# Control_module.net
KiCad netlist of a schematic drawn in Altium Designer
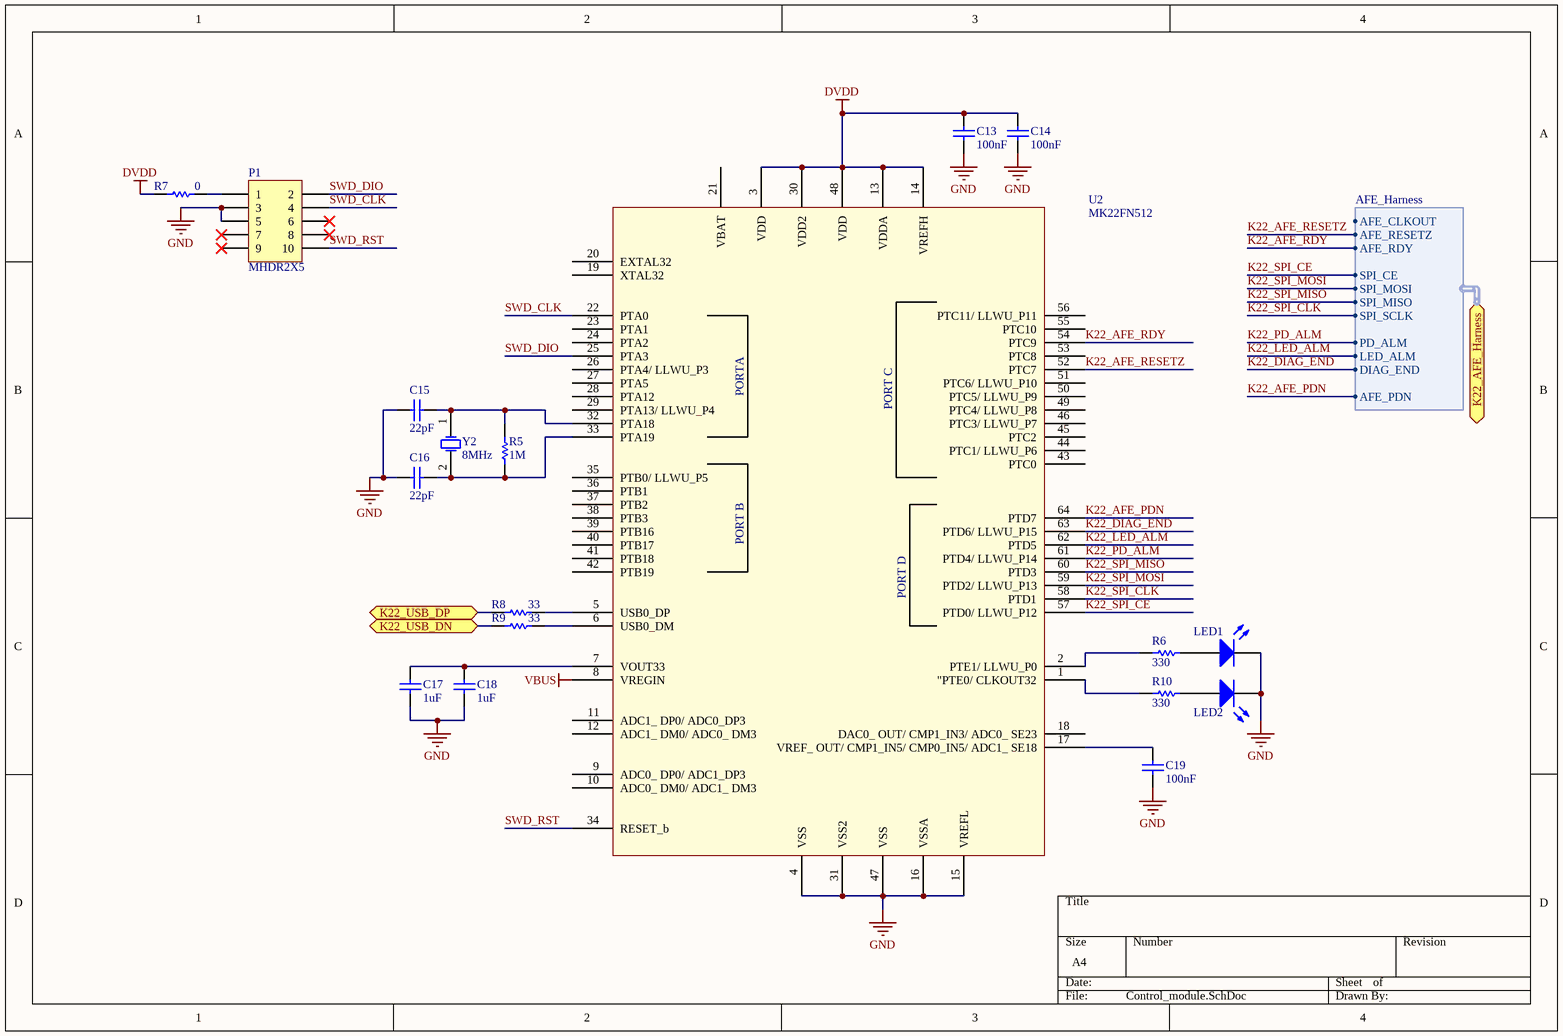
[diagram p0: Control_module.SchDoc]

(export (version "E")
  (design (tool "Eeschema 10.0.6"))
  (components
    (comp (ref "C13")
      (value "100nF")
      (footprint "6-0805_M")
      (description "Capacitor")
      (fields (field (name "Comment") "Cap") (field (name "PUBLISHER") "Altium Limited"))
      (libsource (lib "Miscellaneous Devices") (part "Cap"))
    )
    (comp (ref "C14")
      (value "100nF")
      (footprint "6-0805_M")
      (description "Capacitor")
      (fields (field (name "Comment") "Cap") (field (name "PUBLISHER") "Altium Limited"))
      (libsource (lib "Miscellaneous Devices") (part "Cap"))
    )
    (comp (ref "C15")
      (value "22pF")
      (footprint "6-0805_M")
      (description "Capacitor")
      (fields (field (name "Comment") "Cap") (field (name "PUBLISHER") "Altium Limited"))
      (libsource (lib "Miscellaneous Devices") (part "Cap"))
    )
    (comp (ref "C16")
      (value "22pF")
      (footprint "6-0805_M")
      (description "Capacitor")
      (fields (field (name "Comment") "Cap") (field (name "PUBLISHER") "Altium Limited"))
      (libsource (lib "Miscellaneous Devices") (part "Cap"))
    )
    (comp (ref "C17")
      (value "1uF")
      (footprint "6-0805_M")
      (description "Capacitor")
      (fields (field (name "Comment") "Cap") (field (name "PUBLISHER") "Altium Limited"))
      (libsource (lib "Miscellaneous Devices") (part "Cap"))
    )
    (comp (ref "C18")
      (value "1uF")
      (footprint "6-0805_M")
      (description "Capacitor")
      (fields (field (name "Comment") "Cap") (field (name "PUBLISHER") "Altium Limited"))
      (libsource (lib "Miscellaneous Devices") (part "Cap"))
    )
    (comp (ref "C19")
      (value "100nF")
      (footprint "6-0805_M")
      (description "Capacitor")
      (fields (field (name "Comment") "Cap") (field (name "PUBLISHER") "Altium Limited"))
      (libsource (lib "Miscellaneous Devices") (part "Cap"))
    )
    (comp (ref "LED1")
      (value "LED0")
      (footprint "6-0805_M")
      (description "Typical INFRARED GaAs LED")
      (fields (field (name "PUBLISHER") "Altium Limited"))
      (libsource (lib "Miscellaneous Devices") (part "LED0"))
    )
    (comp (ref "LED2")
      (value "LED0")
      (footprint "6-0805_M")
      (description "Typical INFRARED GaAs LED")
      (fields (field (name "PUBLISHER") "Altium Limited"))
      (libsource (lib "Miscellaneous Devices") (part "LED0"))
    )
    (comp (ref "P1")
      (value "MHDR2X5")
      (footprint "MHDR2X5")
      (description "Header, 5-Pin, Dual row")
      (fields (field (name "PUBLISHER") "Altium Limited"))
      (libsource (lib "Miscellaneous Connectors") (part "MHDR2X5"))
    )
    (comp (ref "R5")
      (value "1M")
      (footprint "6-0805_M")
      (description "Resistor")
      (fields (field (name "Comment") "Res1") (field (name "PUBLISHER") "Altium Limited"))
      (libsource (lib "Miscellaneous Devices") (part "Res1"))
    )
    (comp (ref "R6")
      (value "330")
      (footprint "6-0805_M")
      (description "Resistor")
      (fields (field (name "Comment") "Res1") (field (name "PUBLISHER") "Altium Limited"))
      (libsource (lib "Miscellaneous Devices") (part "Res1"))
    )
    (comp (ref "R7")
      (value "0")
      (footprint "6-0805_M")
      (description "Resistor")
      (fields (field (name "Comment") "Res1") (field (name "PUBLISHER") "Altium Limited"))
      (libsource (lib "Miscellaneous Devices") (part "Res1"))
    )
    (comp (ref "R8")
      (value "33")
      (footprint "6-0805_M")
      (description "Resistor")
      (fields (field (name "Comment") "Res1") (field (name "PUBLISHER") "Altium Limited"))
      (libsource (lib "Miscellaneous Devices") (part "Res1"))
    )
    (comp (ref "R9")
      (value "33")
      (footprint "6-0805_M")
      (description "Resistor")
      (fields (field (name "Comment") "Res1") (field (name "PUBLISHER") "Altium Limited"))
      (libsource (lib "Miscellaneous Devices") (part "Res1"))
    )
    (comp (ref "R10")
      (value "330")
      (footprint "6-0805_M")
      (description "Resistor")
      (fields (field (name "Comment") "Res1") (field (name "PUBLISHER") "Altium Limited"))
      (libsource (lib "Miscellaneous Devices") (part "Res1"))
    )
    (comp (ref "U2")
      (value "MK22FN512")
      (footprint "MK22FN512_TSQFP50P1200X1200X160-64N")
      (description "120 MHz Cortex-M4 Based Microcontroller with FPU")
      (libsource (lib "MK22FN512") (part "MK22FN512"))
    )
    (comp (ref "Y2")
      (value "8MHz")
      (footprint "Crystal SMD")
      (description "Crystal Oscillator")
      (fields (field (name "PUBLISHER") "Altium Limited"))
      (libsource (lib "Miscellaneous Devices") (part "XTAL"))
    )
  )
  (nets
    (net (code "2") (name "/K22_AFE_PDN") (class "Default")
      (node (ref "U2") (pin "64") (pinfunction "PTD7_64") (pintype "passive"))
    )
    (net (code "3") (name "/K22_AFE_RDY") (class "Default")
      (node (ref "U2") (pin "54") (pinfunction "PTC9_54") (pintype "passive"))
    )
    (net (code "4") (name "/K22_AFE_RESETZ") (class "Default")
      (node (ref "U2") (pin "52") (pinfunction "PTC7_52") (pintype "passive"))
    )
    (net (code "5") (name "/K22_DIAG_END") (class "Default")
      (node (ref "U2") (pin "63") (pinfunction "PTD6/_LLWU_P15_63") (pintype "passive"))
    )
    (net (code "6") (name "/K22_LED_ALM") (class "Default")
      (node (ref "U2") (pin "62") (pinfunction "PTD5_62") (pintype "passive"))
    )
    (net (code "7") (name "/K22_PD_ALM") (class "Default")
      (node (ref "U2") (pin "61") (pinfunction "PTD4/_LLWU_P14_61") (pintype "passive"))
    )
    (net (code "8") (name "/K22_SPI_CE") (class "Default")
      (node (ref "U2") (pin "57") (pinfunction "PTD0/_LLWU_P12_57") (pintype "passive"))
    )
    (net (code "9") (name "/K22_SPI_CLK") (class "Default")
      (node (ref "U2") (pin "58") (pinfunction "PTD1_58") (pintype "passive"))
    )
    (net (code "10") (name "/K22_SPI_MISO") (class "Default")
      (node (ref "U2") (pin "60") (pinfunction "PTD3_60") (pintype "passive"))
    )
    (net (code "11") (name "/K22_SPI_MOSI") (class "Default")
      (node (ref "U2") (pin "59") (pinfunction "PTD2/_LLWU_P13_59") (pintype "passive"))
    )
    (net (code "12") (name "/K22_USB_DN") (class "Default")
      (node (ref "R9") (pin "1") (pinfunction "1_1") (pintype "passive"))
    )
    (net (code "13") (name "/K22_USB_DP") (class "Default")
      (node (ref "R8") (pin "1") (pinfunction "1_1") (pintype "passive"))
    )
    (net (code "14") (name "/SWD_CLK") (class "Default")
      (node (ref "P1") (pin "4") (pinfunction "4_4") (pintype "passive"))
      (node (ref "U2") (pin "22") (pinfunction "PTA0_22") (pintype "passive"))
    )
    (net (code "15") (name "/SWD_DIO") (class "Default")
      (node (ref "P1") (pin "2") (pinfunction "2_2") (pintype "passive"))
      (node (ref "U2") (pin "25") (pinfunction "PTA3_25") (pintype "passive"))
    )
    (net (code "16") (name "/SWD_RST") (class "Default")
      (node (ref "P1") (pin "10") (pinfunction "10_10") (pintype "passive"))
      (node (ref "U2") (pin "34") (pinfunction "RESET_b_34") (pintype "passive"))
    )
    (net (code "18") (name "DVDD") (class "Default")
      (node (ref "C13") (pin "1") (pinfunction "1_1") (pintype "passive"))
      (node (ref "C14") (pin "1") (pinfunction "1_1") (pintype "passive"))
      (node (ref "R7") (pin "1") (pinfunction "1_1") (pintype "passive"))
      (node (ref "U2") (pin "13") (pinfunction "VDDA_13") (pintype "passive"))
      (node (ref "U2") (pin "14") (pinfunction "VREFH_14") (pintype "passive"))
      (node (ref "U2") (pin "3") (pinfunction "VDD_3") (pintype "passive"))
      (node (ref "U2") (pin "30") (pinfunction "VDD2_30") (pintype "passive"))
      (node (ref "U2") (pin "48") (pinfunction "VDD_48") (pintype "passive"))
    )
    (net (code "19") (name "GND") (class "Default")
      (node (ref "C13") (pin "2") (pinfunction "2_2") (pintype "passive"))
      (node (ref "C14") (pin "2") (pinfunction "2_2") (pintype "passive"))
      (node (ref "C15") (pin "1") (pinfunction "1_1") (pintype "passive"))
      (node (ref "C16") (pin "1") (pinfunction "1_1") (pintype "passive"))
      (node (ref "C17") (pin "1") (pinfunction "1_1") (pintype "passive"))
      (node (ref "C18") (pin "1") (pinfunction "1_1") (pintype "passive"))
      (node (ref "C19") (pin "1") (pinfunction "1_1") (pintype "passive"))
      (node (ref "LED1") (pin "2") (pinfunction "K_2") (pintype "passive"))
      (node (ref "LED2") (pin "2") (pinfunction "K_2") (pintype "passive"))
      (node (ref "P1") (pin "3") (pinfunction "3_3") (pintype "passive"))
      (node (ref "P1") (pin "5") (pinfunction "5_5") (pintype "passive"))
      (node (ref "U2") (pin "15") (pinfunction "VREFL_15") (pintype "passive"))
      (node (ref "U2") (pin "16") (pinfunction "VSSA_16") (pintype "passive"))
      (node (ref "U2") (pin "31") (pinfunction "VSS2_31") (pintype "passive"))
      (node (ref "U2") (pin "4") (pinfunction "VSS_4") (pintype "passive"))
      (node (ref "U2") (pin "47") (pinfunction "VSS_47") (pintype "passive"))
    )
    (net (code "20") (name "Net-(LED1-A)") (class "Default")
      (node (ref "LED1") (pin "1") (pinfunction "A_1") (pintype "passive"))
      (node (ref "R6") (pin "2") (pinfunction "2_2") (pintype "passive"))
    )
    (net (code "21") (name "Net-(LED2-A)") (class "Default")
      (node (ref "LED2") (pin "1") (pinfunction "A_1") (pintype "passive"))
      (node (ref "R10") (pin "2") (pinfunction "2_2") (pintype "passive"))
    )
    (net (code "22") (name "Net-(P1-Pad1)") (class "Default")
      (node (ref "P1") (pin "1") (pinfunction "1_1") (pintype "passive"))
      (node (ref "R7") (pin "2") (pinfunction "2_2") (pintype "passive"))
    )
    (net (code "23") (name "Net-(U2-\"PTE0{slash}_CLKOUT32)") (class "Default")
      (node (ref "R10") (pin "1") (pinfunction "1_1") (pintype "passive"))
      (node (ref "U2") (pin "1") (pinfunction "\"PTE0/_CLKOUT32_1") (pintype "passive"))
    )
    (net (code "24") (name "Net-(U2-PTA18)") (class "Default")
      (node (ref "C15") (pin "2") (pinfunction "2_2") (pintype "passive"))
      (node (ref "R5") (pin "1") (pinfunction "1_1") (pintype "passive"))
      (node (ref "U2") (pin "32") (pinfunction "PTA18_32") (pintype "passive"))
      (node (ref "Y2") (pin "1") (pinfunction "OSC1_1") (pintype "passive"))
    )
    (net (code "25") (name "Net-(U2-PTA19)") (class "Default")
      (node (ref "C16") (pin "2") (pinfunction "2_2") (pintype "passive"))
      (node (ref "R5") (pin "2") (pinfunction "2_2") (pintype "passive"))
      (node (ref "U2") (pin "33") (pinfunction "PTA19_33") (pintype "passive"))
      (node (ref "Y2") (pin "2") (pinfunction "OSC2_2") (pintype "passive"))
    )
    (net (code "26") (name "Net-(U2-PTE1{slash}_LLWU_P0)") (class "Default")
      (node (ref "R6") (pin "1") (pinfunction "1_1") (pintype "passive"))
      (node (ref "U2") (pin "2") (pinfunction "PTE1/_LLWU_P0_2") (pintype "passive"))
    )
    (net (code "27") (name "Net-(U2-USB0_DM)") (class "Default")
      (node (ref "R9") (pin "2") (pinfunction "2_2") (pintype "passive"))
      (node (ref "U2") (pin "6") (pinfunction "USB0_DM_6") (pintype "passive"))
    )
    (net (code "28") (name "Net-(U2-USB0_DP)") (class "Default")
      (node (ref "R8") (pin "2") (pinfunction "2_2") (pintype "passive"))
      (node (ref "U2") (pin "5") (pinfunction "USB0_DP_5") (pintype "passive"))
    )
    (net (code "29") (name "Net-(U2-VOUT33)") (class "Default")
      (node (ref "C17") (pin "2") (pinfunction "2_2") (pintype "passive"))
      (node (ref "C18") (pin "2") (pinfunction "2_2") (pintype "passive"))
      (node (ref "U2") (pin "7") (pinfunction "VOUT33_7") (pintype "passive"))
    )
    (net (code "30") (name "Net-(U2-VREF__OUT{slash}_CMP1_IN5{slash}_CMP0_IN5{slash}_ADC1__SE18)") (class "Default")
      (node (ref "C19") (pin "2") (pinfunction "2_2") (pintype "passive"))
      (node (ref "U2") (pin "17") (pinfunction "VREF__OUT/_CMP1_IN5/_CMP0_IN5/_ADC1__SE18_17") (pintype "passive"))
    )
    (net (code "31") (name "VBUS") (class "Default")
      (node (ref "U2") (pin "8") (pinfunction "VREGIN_8") (pintype "passive"))
    )
    (net (code "32") (name "unconnected-(P1-Pad6)") (class "Default")
      (node (ref "P1") (pin "6") (pinfunction "6_6") (pintype "passive+no_connect"))
    )
    (net (code "33") (name "unconnected-(P1-Pad7)") (class "Default")
      (node (ref "P1") (pin "7") (pinfunction "7_7") (pintype "passive+no_connect"))
    )
    (net (code "34") (name "unconnected-(P1-Pad8)") (class "Default")
      (node (ref "P1") (pin "8") (pinfunction "8_8") (pintype "passive+no_connect"))
    )
    (net (code "35") (name "unconnected-(P1-Pad9)") (class "Default")
      (node (ref "P1") (pin "9") (pinfunction "9_9") (pintype "passive+no_connect"))
    )
    (net (code "36") (name "unconnected-(U2-ADC0__DM0{slash}_ADC1__DM3-Pad10)") (class "Default")
      (node (ref "U2") (pin "10") (pinfunction "ADC0__DM0/_ADC1__DM3_10") (pintype "passive"))
    )
    (net (code "37") (name "unconnected-(U2-ADC0__DP0{slash}_ADC1_DP3-Pad9)") (class "Default")
      (node (ref "U2") (pin "9") (pinfunction "ADC0__DP0/_ADC1_DP3_9") (pintype "passive"))
    )
    (net (code "38") (name "unconnected-(U2-ADC1__DM0{slash}_ADC0__DM3-Pad12)") (class "Default")
      (node (ref "U2") (pin "12") (pinfunction "ADC1__DM0/_ADC0__DM3_12") (pintype "passive"))
    )
    (net (code "39") (name "unconnected-(U2-ADC1__DP0{slash}_ADC0_DP3-Pad11)") (class "Default")
      (node (ref "U2") (pin "11") (pinfunction "ADC1__DP0/_ADC0_DP3_11") (pintype "passive"))
    )
    (net (code "40") (name "unconnected-(U2-DAC0__OUT{slash}_CMP1_IN3{slash}_ADC0__SE23-Pad18)") (class "Default")
      (node (ref "U2") (pin "18") (pinfunction "DAC0__OUT/_CMP1_IN3/_ADC0__SE23_18") (pintype "passive"))
    )
    (net (code "41") (name "unconnected-(U2-EXTAL32-Pad20)") (class "Default")
      (node (ref "U2") (pin "20") (pinfunction "EXTAL32_20") (pintype "passive"))
    )
    (net (code "42") (name "unconnected-(U2-PTA1-Pad23)") (class "Default")
      (node (ref "U2") (pin "23") (pinfunction "PTA1_23") (pintype "passive"))
    )
    (net (code "43") (name "unconnected-(U2-PTA2-Pad24)") (class "Default")
      (node (ref "U2") (pin "24") (pinfunction "PTA2_24") (pintype "passive"))
    )
    (net (code "44") (name "unconnected-(U2-PTA4{slash}_LLWU_P3-Pad26)") (class "Default")
      (node (ref "U2") (pin "26") (pinfunction "PTA4/_LLWU_P3_26") (pintype "passive"))
    )
    (net (code "45") (name "unconnected-(U2-PTA5-Pad27)") (class "Default")
      (node (ref "U2") (pin "27") (pinfunction "PTA5_27") (pintype "passive"))
    )
    (net (code "46") (name "unconnected-(U2-PTA12-Pad28)") (class "Default")
      (node (ref "U2") (pin "28") (pinfunction "PTA12_28") (pintype "passive"))
    )
    (net (code "47") (name "unconnected-(U2-PTA13{slash}_LLWU_P4-Pad29)") (class "Default")
      (node (ref "U2") (pin "29") (pinfunction "PTA13/_LLWU_P4_29") (pintype "passive"))
    )
    (net (code "48") (name "unconnected-(U2-PTB0{slash}_LLWU_P5-Pad35)") (class "Default")
      (node (ref "U2") (pin "35") (pinfunction "PTB0/_LLWU_P5_35") (pintype "passive"))
    )
    (net (code "49") (name "unconnected-(U2-PTB1-Pad36)") (class "Default")
      (node (ref "U2") (pin "36") (pinfunction "PTB1_36") (pintype "passive"))
    )
    (net (code "50") (name "unconnected-(U2-PTB2-Pad37)") (class "Default")
      (node (ref "U2") (pin "37") (pinfunction "PTB2_37") (pintype "passive"))
    )
    (net (code "51") (name "unconnected-(U2-PTB3-Pad38)") (class "Default")
      (node (ref "U2") (pin "38") (pinfunction "PTB3_38") (pintype "passive"))
    )
    (net (code "52") (name "unconnected-(U2-PTB16-Pad39)") (class "Default")
      (node (ref "U2") (pin "39") (pinfunction "PTB16_39") (pintype "passive"))
    )
    (net (code "53") (name "unconnected-(U2-PTB17-Pad40)") (class "Default")
      (node (ref "U2") (pin "40") (pinfunction "PTB17_40") (pintype "passive"))
    )
    (net (code "54") (name "unconnected-(U2-PTB18-Pad41)") (class "Default")
      (node (ref "U2") (pin "41") (pinfunction "PTB18_41") (pintype "passive"))
    )
    (net (code "55") (name "unconnected-(U2-PTB19-Pad42)") (class "Default")
      (node (ref "U2") (pin "42") (pinfunction "PTB19_42") (pintype "passive"))
    )
    (net (code "56") (name "unconnected-(U2-PTC0-Pad43)") (class "Default")
      (node (ref "U2") (pin "43") (pinfunction "PTC0_43") (pintype "passive"))
    )
    (net (code "57") (name "unconnected-(U2-PTC1{slash}_LLWU_P6-Pad44)") (class "Default")
      (node (ref "U2") (pin "44") (pinfunction "PTC1/_LLWU_P6_44") (pintype "passive"))
    )
    (net (code "58") (name "unconnected-(U2-PTC2-Pad45)") (class "Default")
      (node (ref "U2") (pin "45") (pinfunction "PTC2_45") (pintype "passive"))
    )
    (net (code "59") (name "unconnected-(U2-PTC3{slash}_LLWU_P7-Pad46)") (class "Default")
      (node (ref "U2") (pin "46") (pinfunction "PTC3/_LLWU_P7_46") (pintype "passive"))
    )
    (net (code "60") (name "unconnected-(U2-PTC4{slash}_LLWU_P8-Pad49)") (class "Default")
      (node (ref "U2") (pin "49") (pinfunction "PTC4/_LLWU_P8_49") (pintype "passive"))
    )
    (net (code "61") (name "unconnected-(U2-PTC5{slash}_LLWU_P9-Pad50)") (class "Default")
      (node (ref "U2") (pin "50") (pinfunction "PTC5/_LLWU_P9_50") (pintype "passive"))
    )
    (net (code "62") (name "unconnected-(U2-PTC6{slash}_LLWU_P10-Pad51)") (class "Default")
      (node (ref "U2") (pin "51") (pinfunction "PTC6/_LLWU_P10_51") (pintype "passive"))
    )
    (net (code "63") (name "unconnected-(U2-PTC8-Pad53)") (class "Default")
      (node (ref "U2") (pin "53") (pinfunction "PTC8_53") (pintype "passive"))
    )
    (net (code "64") (name "unconnected-(U2-PTC10-Pad55)") (class "Default")
      (node (ref "U2") (pin "55") (pinfunction "PTC10_55") (pintype "passive"))
    )
    (net (code "65") (name "unconnected-(U2-PTC11{slash}_LLWU_P11-Pad56)") (class "Default")
      (node (ref "U2") (pin "56") (pinfunction "PTC11/_LLWU_P11_56") (pintype "passive"))
    )
    (net (code "66") (name "unconnected-(U2-VBAT-Pad21)") (class "Default")
      (node (ref "U2") (pin "21") (pinfunction "VBAT_21") (pintype "passive"))
    )
    (net (code "67") (name "unconnected-(U2-XTAL32-Pad19)") (class "Default")
      (node (ref "U2") (pin "19") (pinfunction "XTAL32_19") (pintype "passive"))
    )
  )
)
